# Power.net
KiCad netlist of a schematic drawn in Altium Designer
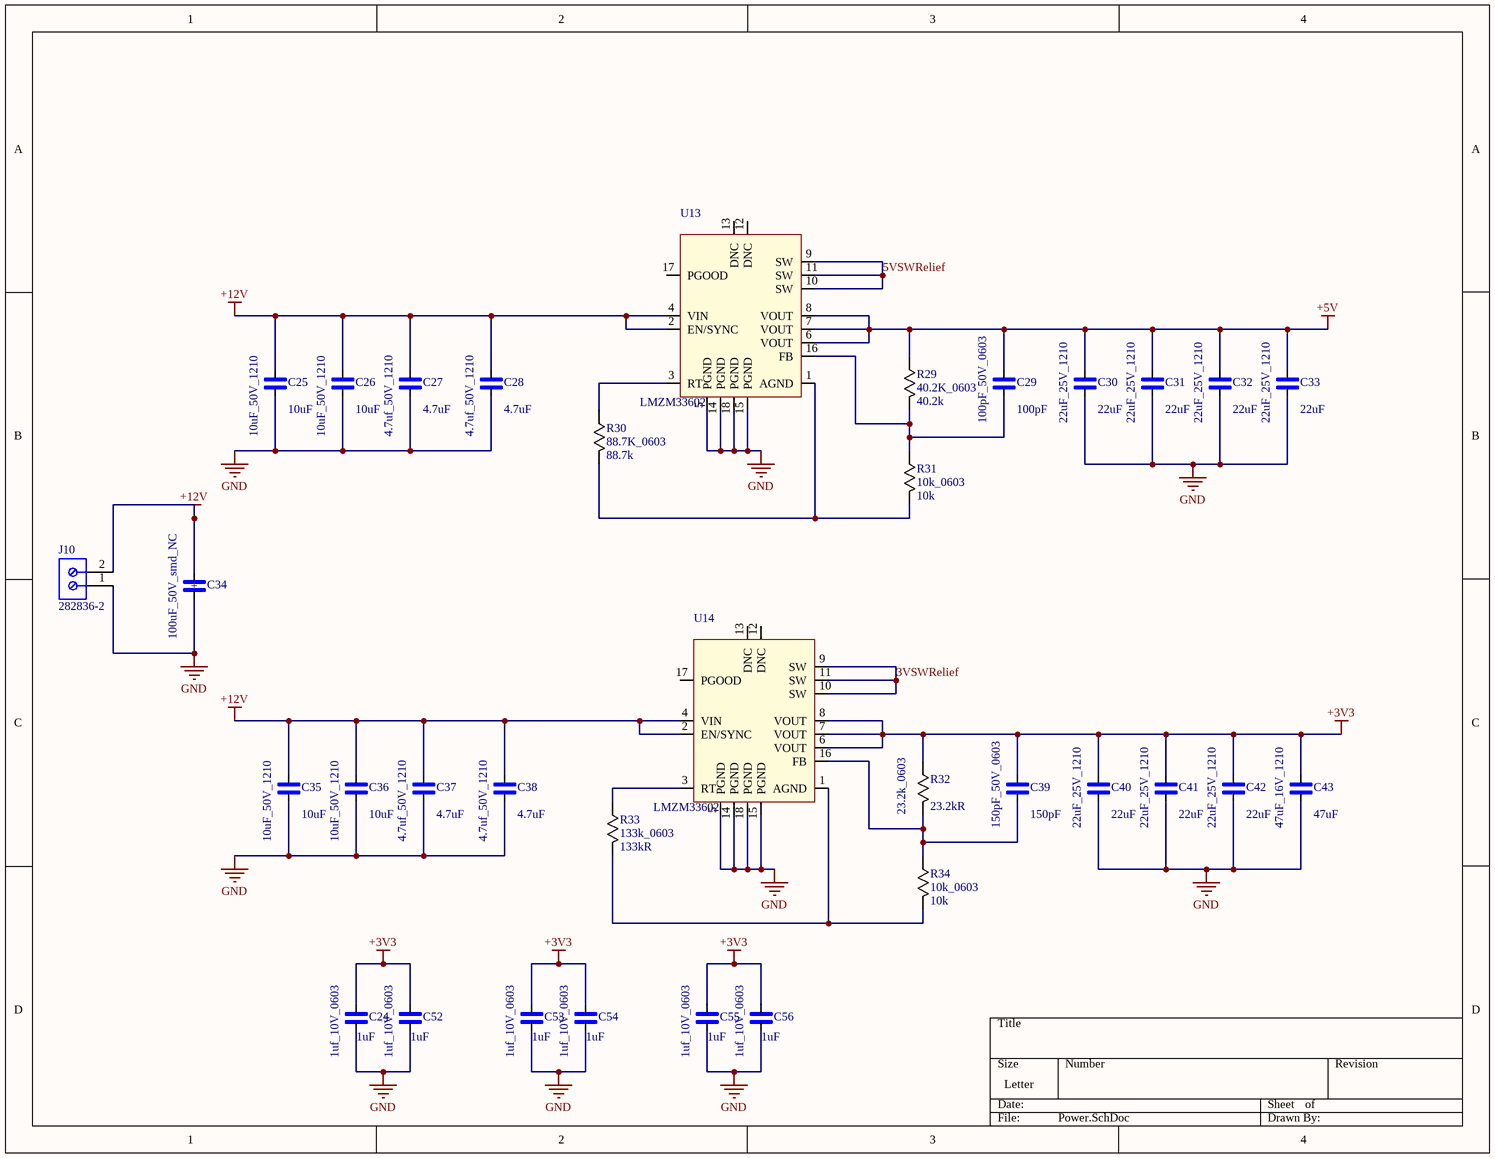
[diagram p0: Power.SchDoc]

(export (version "E")
  (design (tool "Eeschema 10.0.6"))
  (components
    (comp (ref "C24")
      (value "1uf_10V_0603")
      (footprint "0603")
      (fields
        (field (name "MANUFACTURER") "Murata")
        (field (name "MANUFACTURER PART NUMBER") "GRM188R61A105KA61J")
        (field (name "TOLERANCE") "10%")
        (field (name "CAPACITANCE") "1uF")
      )
      (libsource (lib "Capacitors") (part "1uf_10V_0603"))
    )
    (comp (ref "C25")
      (value "10uF_50V_1210")
      (footprint "1210")
      (fields
        (field (name "MANUFACTURER") "Murata")
        (field (name "MANUFACTURER PART NUMBER") "GRM32ER71H106KA12L")
        (field (name "TOLERANCE") "10%")
        (field (name "CAPACITANCE") "10uF")
      )
      (libsource (lib "Capacitors") (part "10uF_50V_1210"))
    )
    (comp (ref "C26")
      (value "10uF_50V_1210")
      (footprint "1210")
      (fields
        (field (name "MANUFACTURER") "Murata")
        (field (name "MANUFACTURER PART NUMBER") "GRM32ER71H106KA12L")
        (field (name "TOLERANCE") "10%")
        (field (name "CAPACITANCE") "10uF")
      )
      (libsource (lib "Capacitors") (part "10uF_50V_1210"))
    )
    (comp (ref "C27")
      (value "4.7uf_50V_1210")
      (footprint "1210")
      (fields
        (field (name "MANUFACTURER") "Murata")
        (field (name "MANUFACTURER PART NUMBER") "GRM32ER71H475KA88L")
        (field (name "TOLERANCE") "10%")
        (field (name "CAPACITANCE") "4.7uF")
      )
      (libsource (lib "Capacitors") (part "4.7uf_50V_1210"))
    )
    (comp (ref "C28")
      (value "4.7uf_50V_1210")
      (footprint "1210")
      (fields
        (field (name "MANUFACTURER") "Murata")
        (field (name "MANUFACTURER PART NUMBER") "GRM32ER71H475KA88L")
        (field (name "TOLERANCE") "10%")
        (field (name "CAPACITANCE") "4.7uF")
      )
      (libsource (lib "Capacitors") (part "4.7uf_50V_1210"))
    )
    (comp (ref "C29")
      (value "100pF_50V_0603")
      (footprint "0603")
      (fields
        (field (name "MANUFACTURER") "Murata")
        (field (name "MANUFACTURER PART NUMBER") "GRM1885C1H101JA01D")
        (field (name "TOLERANCE") "5%")
        (field (name "CAPACITANCE") "100pF")
      )
      (libsource (lib "Capacitors") (part "100pF_50V_0603"))
    )
    (comp (ref "C30")
      (value "22uF_25V_1210")
      (footprint "1210")
      (fields
        (field (name "MANUFACTURER") "Murata")
        (field (name "MANUFACTURER PART NUMBER") "GRM32ER71E226KE15L")
        (field (name "TOLERANCE") "10%")
        (field (name "CAPACITANCE") "22uF")
      )
      (libsource (lib "Capacitors") (part "22uF_25V_1210"))
    )
    (comp (ref "C31")
      (value "22uF_25V_1210")
      (footprint "1210")
      (fields
        (field (name "MANUFACTURER") "Murata")
        (field (name "MANUFACTURER PART NUMBER") "GRM32ER71E226KE15L")
        (field (name "TOLERANCE") "10%")
        (field (name "CAPACITANCE") "22uF")
      )
      (libsource (lib "Capacitors") (part "22uF_25V_1210"))
    )
    (comp (ref "C32")
      (value "22uF_25V_1210")
      (footprint "1210")
      (fields
        (field (name "MANUFACTURER") "Murata")
        (field (name "MANUFACTURER PART NUMBER") "GRM32ER71E226KE15L")
        (field (name "TOLERANCE") "10%")
        (field (name "CAPACITANCE") "22uF")
      )
      (libsource (lib "Capacitors") (part "22uF_25V_1210"))
    )
    (comp (ref "C33")
      (value "22uF_25V_1210")
      (footprint "1210")
      (fields
        (field (name "MANUFACTURER") "Murata")
        (field (name "MANUFACTURER PART NUMBER") "GRM32ER71E226KE15L")
        (field (name "TOLERANCE") "10%")
        (field (name "CAPACITANCE") "22uF")
      )
      (libsource (lib "Capacitors") (part "22uF_25V_1210"))
    )
    (comp (ref "C34")
      (value "100uF_50V_smd_NC")
      (footprint "CAPAE120103X105M")
      (fields
        (field (name "MANUFACTURER") "Panasonic")
        (field (name "MANUFACTURER PART NUMBER") "EEH-ZA1H101P")
        (field (name "TOLERANCE") "20%")
      )
      (libsource (lib "Capacitors") (part "100uF_50V_smd_NC"))
    )
    (comp (ref "C35")
      (value "10uF_50V_1210")
      (footprint "1210")
      (fields
        (field (name "MANUFACTURER") "Murata")
        (field (name "MANUFACTURER PART NUMBER") "GRM32ER71H106KA12L")
        (field (name "TOLERANCE") "10%")
        (field (name "CAPACITANCE") "10uF")
      )
      (libsource (lib "Capacitors") (part "10uF_50V_1210"))
    )
    (comp (ref "C36")
      (value "10uF_50V_1210")
      (footprint "1210")
      (fields
        (field (name "MANUFACTURER") "Murata")
        (field (name "MANUFACTURER PART NUMBER") "GRM32ER71H106KA12L")
        (field (name "TOLERANCE") "10%")
        (field (name "CAPACITANCE") "10uF")
      )
      (libsource (lib "Capacitors") (part "10uF_50V_1210"))
    )
    (comp (ref "C37")
      (value "4.7uf_50V_1210")
      (footprint "1210")
      (fields
        (field (name "MANUFACTURER") "Murata")
        (field (name "MANUFACTURER PART NUMBER") "GRM32ER71H475KA88L")
        (field (name "TOLERANCE") "10%")
        (field (name "CAPACITANCE") "4.7uF")
      )
      (libsource (lib "Capacitors") (part "4.7uf_50V_1210"))
    )
    (comp (ref "C38")
      (value "4.7uf_50V_1210")
      (footprint "1210")
      (fields
        (field (name "MANUFACTURER") "Murata")
        (field (name "MANUFACTURER PART NUMBER") "GRM32ER71H475KA88L")
        (field (name "TOLERANCE") "10%")
        (field (name "CAPACITANCE") "4.7uF")
      )
      (libsource (lib "Capacitors") (part "4.7uf_50V_1210"))
    )
    (comp (ref "C39")
      (value "150pF_50V_0603")
      (footprint "0603")
      (fields
        (field (name "MANUFACTURER") "Murata")
        (field (name "MANUFACTURER PART NUMBER") "GRM1885C1H151JA01D")
        (field (name "TOLERANCE") "5%")
        (field (name "CAPACITANCE") "150pF")
      )
      (libsource (lib "Capacitors") (part "150pF_50V_0603"))
    )
    (comp (ref "C40")
      (value "22uF_25V_1210")
      (footprint "1210")
      (fields
        (field (name "MANUFACTURER") "Murata")
        (field (name "MANUFACTURER PART NUMBER") "GRM32ER71E226KE15L")
        (field (name "TOLERANCE") "10%")
        (field (name "CAPACITANCE") "22uF")
      )
      (libsource (lib "Capacitors") (part "22uF_25V_1210"))
    )
    (comp (ref "C41")
      (value "22uF_25V_1210")
      (footprint "1210")
      (fields
        (field (name "MANUFACTURER") "Murata")
        (field (name "MANUFACTURER PART NUMBER") "GRM32ER71E226KE15L")
        (field (name "TOLERANCE") "10%")
        (field (name "CAPACITANCE") "22uF")
      )
      (libsource (lib "Capacitors") (part "22uF_25V_1210"))
    )
    (comp (ref "C42")
      (value "22uF_25V_1210")
      (footprint "1210")
      (fields
        (field (name "MANUFACTURER") "Murata")
        (field (name "MANUFACTURER PART NUMBER") "GRM32ER71E226KE15L")
        (field (name "TOLERANCE") "10%")
        (field (name "CAPACITANCE") "22uF")
      )
      (libsource (lib "Capacitors") (part "22uF_25V_1210"))
    )
    (comp (ref "C43")
      (value "47uF_16V_1210")
      (footprint "1210")
      (fields
        (field (name "MANUFACTURER") "Murata")
        (field (name "MANUFACTURER PART NUMBER") "GRM32ER61C476KE15L")
        (field (name "TOLERANCE") "10%")
        (field (name "CAPACITANCE") "47uF")
      )
      (libsource (lib "Capacitors") (part "47uF_16V_1210"))
    )
    (comp (ref "C52")
      (value "1uf_10V_0603")
      (footprint "0603")
      (fields
        (field (name "MANUFACTURER") "Murata")
        (field (name "MANUFACTURER PART NUMBER") "GRM188R61A105KA61J")
        (field (name "TOLERANCE") "10%")
        (field (name "CAPACITANCE") "1uF")
      )
      (libsource (lib "Capacitors") (part "1uf_10V_0603"))
    )
    (comp (ref "C53")
      (value "1uf_10V_0603")
      (footprint "0603")
      (fields
        (field (name "MANUFACTURER") "Murata")
        (field (name "MANUFACTURER PART NUMBER") "GRM188R61A105KA61J")
        (field (name "TOLERANCE") "10%")
        (field (name "CAPACITANCE") "1uF")
      )
      (libsource (lib "Capacitors") (part "1uf_10V_0603"))
    )
    (comp (ref "C54")
      (value "1uf_10V_0603")
      (footprint "0603")
      (fields
        (field (name "MANUFACTURER") "Murata")
        (field (name "MANUFACTURER PART NUMBER") "GRM188R61A105KA61J")
        (field (name "TOLERANCE") "10%")
        (field (name "CAPACITANCE") "1uF")
      )
      (libsource (lib "Capacitors") (part "1uf_10V_0603"))
    )
    (comp (ref "C55")
      (value "1uf_10V_0603")
      (footprint "0603")
      (fields
        (field (name "MANUFACTURER") "Murata")
        (field (name "MANUFACTURER PART NUMBER") "GRM188R61A105KA61J")
        (field (name "TOLERANCE") "10%")
        (field (name "CAPACITANCE") "1uF")
      )
      (libsource (lib "Capacitors") (part "1uf_10V_0603"))
    )
    (comp (ref "C56")
      (value "1uf_10V_0603")
      (footprint "0603")
      (fields
        (field (name "MANUFACTURER") "Murata")
        (field (name "MANUFACTURER PART NUMBER") "GRM188R61A105KA61J")
        (field (name "TOLERANCE") "10%")
        (field (name "CAPACITANCE") "1uF")
      )
      (libsource (lib "Capacitors") (part "1uf_10V_0603"))
    )
    (comp (ref "J10")
      (value "282836-2")
      (footprint "TECO-282836-2_V")
      (description "Female Header, Pitch 5 mm, 1 x 2 Position, Height 10 mm, Tail Length 3.5 mm, Rohs, Bulk")
      (fields (field (name "VOLTAGE") "300V"))
      (libsource (lib "TE Terminal Blocks and Strips") (part "282836-2"))
    )
    (comp (ref "R29")
      (value "40.2K_0603")
      (footprint "0603")
      (fields
        (field (name "MANUFACTURER") "Vishay Dale")
        (field (name "MANUFACTURER PART NUMBER") "M55342E12B40B2RWS")
        (field (name "TOLERANCE") "0.1%")
        (field (name "RESISTANCE") "40.2k")
      )
      (libsource (lib "Resistors") (part "40.2K_0603"))
    )
    (comp (ref "R30")
      (value "88.7K_0603")
      (footprint "0603")
      (fields
        (field (name "MANUFACTURER") "TE Connectivity")
        (field (name "MANUFACTURER PART NUMBER") "8-2176089-5")
        (field (name "TOLERANCE") "0.1%")
        (field (name "RESISTANCE") "88.7k")
      )
      (libsource (lib "Resistors") (part "88.7K_0603"))
    )
    (comp (ref "R31")
      (value "10k_0603")
      (footprint "0603")
      (fields
        (field (name "MANUFACTURER") "Panasonic")
        (field (name "MANUFACTURER PART NUMBER") "ERJ-3EKF1002V")
        (field (name "TOLERANCE") "1%")
        (field (name "RESISTANCE") "10k")
      )
      (libsource (lib "Resistors") (part "10k_0603"))
    )
    (comp (ref "R32")
      (value "23.2k_0603")
      (footprint "0603")
      (fields
        (field (name "MANUFACTURER") "TE Connectivity")
        (field (name "MANUFACTURER PART NUMBER") "3-2176089-1")
        (field (name "TOLERANCE") "0.1%")
        (field (name "RESISTANCE") "23.2kR")
      )
      (libsource (lib "Resistors") (part "23.2k_0603"))
    )
    (comp (ref "R33")
      (value "133k_0603")
      (footprint "0603")
      (fields
        (field (name "MANUFACTURER") "TE Connectivity")
        (field (name "MANUFACTURER PART NUMBER") "2176090-2")
        (field (name "TOLERANCE") "0.1%")
        (field (name "RESISTANCE") "133kR")
      )
      (libsource (lib "Resistors") (part "133k_0603"))
    )
    (comp (ref "R34")
      (value "10k_0603")
      (footprint "0603")
      (fields
        (field (name "MANUFACTURER") "Panasonic")
        (field (name "MANUFACTURER PART NUMBER") "ERJ-3EKF1002V")
        (field (name "TOLERANCE") "1%")
        (field (name "RESISTANCE") "10k")
      )
      (libsource (lib "Resistors") (part "10k_0603"))
    )
    (comp (ref "U13")
      (value "LMZM33602")
      (footprint "QFN50P700X900X410_HS-55N")
      (description "4V to 36V, 2A Step-Down DC/DC Power Module")
      (libsource (lib "Power") (part "LMZM33602"))
    )
    (comp (ref "U14")
      (value "LMZM33602")
      (footprint "QFN50P700X900X410_HS-55N")
      (description "4V to 36V, 2A Step-Down DC/DC Power Module")
      (libsource (lib "Power") (part "LMZM33602"))
    )
  )
  (nets
    (net (code "1") (name "+3V3") (class "Default")
      (node (ref "C24") (pin "2") (pinfunction "2_2") (pintype "passive"))
      (node (ref "C39") (pin "2") (pinfunction "2_2") (pintype "passive"))
      (node (ref "C40") (pin "2") (pinfunction "2_2") (pintype "passive"))
      (node (ref "C41") (pin "2") (pinfunction "2_2") (pintype "passive"))
      (node (ref "C42") (pin "2") (pinfunction "2_2") (pintype "passive"))
      (node (ref "C43") (pin "2") (pinfunction "2_2") (pintype "passive"))
      (node (ref "C52") (pin "2") (pinfunction "2_2") (pintype "passive"))
      (node (ref "C53") (pin "2") (pinfunction "2_2") (pintype "passive"))
      (node (ref "C54") (pin "2") (pinfunction "2_2") (pintype "passive"))
      (node (ref "C55") (pin "2") (pinfunction "2_2") (pintype "passive"))
      (node (ref "C56") (pin "2") (pinfunction "2_2") (pintype "passive"))
      (node (ref "R32") (pin "2") (pinfunction "2_2") (pintype "passive"))
      (node (ref "U14") (pin "6") (pinfunction "VOUT_6") (pintype "passive"))
      (node (ref "U14") (pin "7") (pinfunction "VOUT_7") (pintype "passive"))
      (node (ref "U14") (pin "8") (pinfunction "VOUT_8") (pintype "passive"))
    )
    (net (code "2") (name "+5V") (class "Default")
      (node (ref "C29") (pin "2") (pinfunction "2_2") (pintype "passive"))
      (node (ref "C30") (pin "2") (pinfunction "2_2") (pintype "passive"))
      (node (ref "C31") (pin "2") (pinfunction "2_2") (pintype "passive"))
      (node (ref "C32") (pin "2") (pinfunction "2_2") (pintype "passive"))
      (node (ref "C33") (pin "2") (pinfunction "2_2") (pintype "passive"))
      (node (ref "R29") (pin "2") (pinfunction "2_2") (pintype "passive"))
      (node (ref "U13") (pin "6") (pinfunction "VOUT_6") (pintype "passive"))
      (node (ref "U13") (pin "7") (pinfunction "VOUT_7") (pintype "passive"))
      (node (ref "U13") (pin "8") (pinfunction "VOUT_8") (pintype "passive"))
    )
    (net (code "3") (name "+12V") (class "Default")
      (node (ref "C25") (pin "2") (pinfunction "2_2") (pintype "passive"))
      (node (ref "C26") (pin "2") (pinfunction "2_2") (pintype "passive"))
      (node (ref "C27") (pin "2") (pinfunction "2_2") (pintype "passive"))
      (node (ref "C28") (pin "2") (pinfunction "2_2") (pintype "passive"))
      (node (ref "C34") (pin "1") (pinfunction "+_1") (pintype "passive"))
      (node (ref "C35") (pin "2") (pinfunction "2_2") (pintype "passive"))
      (node (ref "C36") (pin "2") (pinfunction "2_2") (pintype "passive"))
      (node (ref "C37") (pin "2") (pinfunction "2_2") (pintype "passive"))
      (node (ref "C38") (pin "2") (pinfunction "2_2") (pintype "passive"))
      (node (ref "J10") (pin "2") (pinfunction "2_2") (pintype "passive"))
      (node (ref "U13") (pin "2") (pinfunction "EN/SYNC_2") (pintype "passive"))
      (node (ref "U13") (pin "4") (pinfunction "VIN_4") (pintype "passive"))
      (node (ref "U14") (pin "2") (pinfunction "EN/SYNC_2") (pintype "passive"))
      (node (ref "U14") (pin "4") (pinfunction "VIN_4") (pintype "passive"))
    )
    (net (code "4") (name "/3VSWRelief") (class "Default")
      (node (ref "U14") (pin "10") (pinfunction "SW_10") (pintype "passive"))
      (node (ref "U14") (pin "11") (pinfunction "SW_11") (pintype "passive"))
      (node (ref "U14") (pin "9") (pinfunction "SW_9") (pintype "passive"))
    )
    (net (code "5") (name "/5VSWRelief") (class "Default")
      (node (ref "U13") (pin "10") (pinfunction "SW_10") (pintype "passive"))
      (node (ref "U13") (pin "11") (pinfunction "SW_11") (pintype "passive"))
      (node (ref "U13") (pin "9") (pinfunction "SW_9") (pintype "passive"))
    )
    (net (code "6") (name "GND") (class "Default")
      (node (ref "C24") (pin "1") (pinfunction "1_1") (pintype "passive"))
      (node (ref "C25") (pin "1") (pinfunction "1_1") (pintype "passive"))
      (node (ref "C26") (pin "1") (pinfunction "1_1") (pintype "passive"))
      (node (ref "C27") (pin "1") (pinfunction "1_1") (pintype "passive"))
      (node (ref "C28") (pin "1") (pinfunction "1_1") (pintype "passive"))
      (node (ref "C30") (pin "1") (pinfunction "1_1") (pintype "passive"))
      (node (ref "C31") (pin "1") (pinfunction "1_1") (pintype "passive"))
      (node (ref "C32") (pin "1") (pinfunction "1_1") (pintype "passive"))
      (node (ref "C33") (pin "1") (pinfunction "1_1") (pintype "passive"))
      (node (ref "C34") (pin "2") (pinfunction "2_2") (pintype "passive"))
      (node (ref "C35") (pin "1") (pinfunction "1_1") (pintype "passive"))
      (node (ref "C36") (pin "1") (pinfunction "1_1") (pintype "passive"))
      (node (ref "C37") (pin "1") (pinfunction "1_1") (pintype "passive"))
      (node (ref "C38") (pin "1") (pinfunction "1_1") (pintype "passive"))
      (node (ref "C40") (pin "1") (pinfunction "1_1") (pintype "passive"))
      (node (ref "C41") (pin "1") (pinfunction "1_1") (pintype "passive"))
      (node (ref "C42") (pin "1") (pinfunction "1_1") (pintype "passive"))
      (node (ref "C43") (pin "1") (pinfunction "1_1") (pintype "passive"))
      (node (ref "C52") (pin "1") (pinfunction "1_1") (pintype "passive"))
      (node (ref "C53") (pin "1") (pinfunction "1_1") (pintype "passive"))
      (node (ref "C54") (pin "1") (pinfunction "1_1") (pintype "passive"))
      (node (ref "C55") (pin "1") (pinfunction "1_1") (pintype "passive"))
      (node (ref "C56") (pin "1") (pinfunction "1_1") (pintype "passive"))
      (node (ref "J10") (pin "1") (pinfunction "1_1") (pintype "passive"))
      (node (ref "U13") (pin "14") (pinfunction "PGND_14") (pintype "passive"))
      (node (ref "U13") (pin "15") (pinfunction "PGND_15") (pintype "passive"))
      (node (ref "U13") (pin "18") (pinfunction "PGND_18") (pintype "passive"))
      (node (ref "U13") (pin "5") (pinfunction "PGND_5") (pintype "passive"))
      (node (ref "U14") (pin "14") (pinfunction "PGND_14") (pintype "passive"))
      (node (ref "U14") (pin "15") (pinfunction "PGND_15") (pintype "passive"))
      (node (ref "U14") (pin "18") (pinfunction "PGND_18") (pintype "passive"))
      (node (ref "U14") (pin "5") (pinfunction "PGND_5") (pintype "passive"))
    )
    (net (code "7") (name "Net-(U13-AGND)") (class "Default")
      (node (ref "R30") (pin "1") (pinfunction "1_1") (pintype "passive"))
      (node (ref "R31") (pin "1") (pinfunction "1_1") (pintype "passive"))
      (node (ref "U13") (pin "1") (pinfunction "AGND_1") (pintype "passive"))
    )
    (net (code "8") (name "Net-(U13-FB)") (class "Default")
      (node (ref "C29") (pin "1") (pinfunction "1_1") (pintype "passive"))
      (node (ref "R29") (pin "1") (pinfunction "1_1") (pintype "passive"))
      (node (ref "R31") (pin "2") (pinfunction "2_2") (pintype "passive"))
      (node (ref "U13") (pin "16") (pinfunction "FB_16") (pintype "passive"))
    )
    (net (code "9") (name "Net-(U13-RT)") (class "Default")
      (node (ref "R30") (pin "2") (pinfunction "2_2") (pintype "passive"))
      (node (ref "U13") (pin "3") (pinfunction "RT_3") (pintype "passive"))
    )
    (net (code "10") (name "Net-(U14-AGND)") (class "Default")
      (node (ref "R33") (pin "1") (pinfunction "1_1") (pintype "passive"))
      (node (ref "R34") (pin "1") (pinfunction "1_1") (pintype "passive"))
      (node (ref "U14") (pin "1") (pinfunction "AGND_1") (pintype "passive"))
    )
    (net (code "11") (name "Net-(U14-FB)") (class "Default")
      (node (ref "C39") (pin "1") (pinfunction "1_1") (pintype "passive"))
      (node (ref "R32") (pin "1") (pinfunction "1_1") (pintype "passive"))
      (node (ref "R34") (pin "2") (pinfunction "2_2") (pintype "passive"))
      (node (ref "U14") (pin "16") (pinfunction "FB_16") (pintype "passive"))
    )
    (net (code "12") (name "Net-(U14-RT)") (class "Default")
      (node (ref "R33") (pin "2") (pinfunction "2_2") (pintype "passive"))
      (node (ref "U14") (pin "3") (pinfunction "RT_3") (pintype "passive"))
    )
    (net (code "13") (name "unconnected-(U13-DNC-Pad12)") (class "Default")
      (node (ref "U13") (pin "12") (pinfunction "DNC_12") (pintype "passive"))
    )
    (net (code "14") (name "unconnected-(U13-DNC-Pad13)") (class "Default")
      (node (ref "U13") (pin "13") (pinfunction "DNC_13") (pintype "passive"))
    )
    (net (code "15") (name "unconnected-(U13-PGOOD-Pad17)") (class "Default")
      (node (ref "U13") (pin "17") (pinfunction "PGOOD_17") (pintype "passive"))
    )
    (net (code "16") (name "unconnected-(U14-DNC-Pad12)") (class "Default")
      (node (ref "U14") (pin "12") (pinfunction "DNC_12") (pintype "passive"))
    )
    (net (code "17") (name "unconnected-(U14-DNC-Pad13)") (class "Default")
      (node (ref "U14") (pin "13") (pinfunction "DNC_13") (pintype "passive"))
    )
    (net (code "18") (name "unconnected-(U14-PGOOD-Pad17)") (class "Default")
      (node (ref "U14") (pin "17") (pinfunction "PGOOD_17") (pintype "passive"))
    )
  )
)
